# Power.net
KiCad netlist of a schematic drawn in Altium Designer
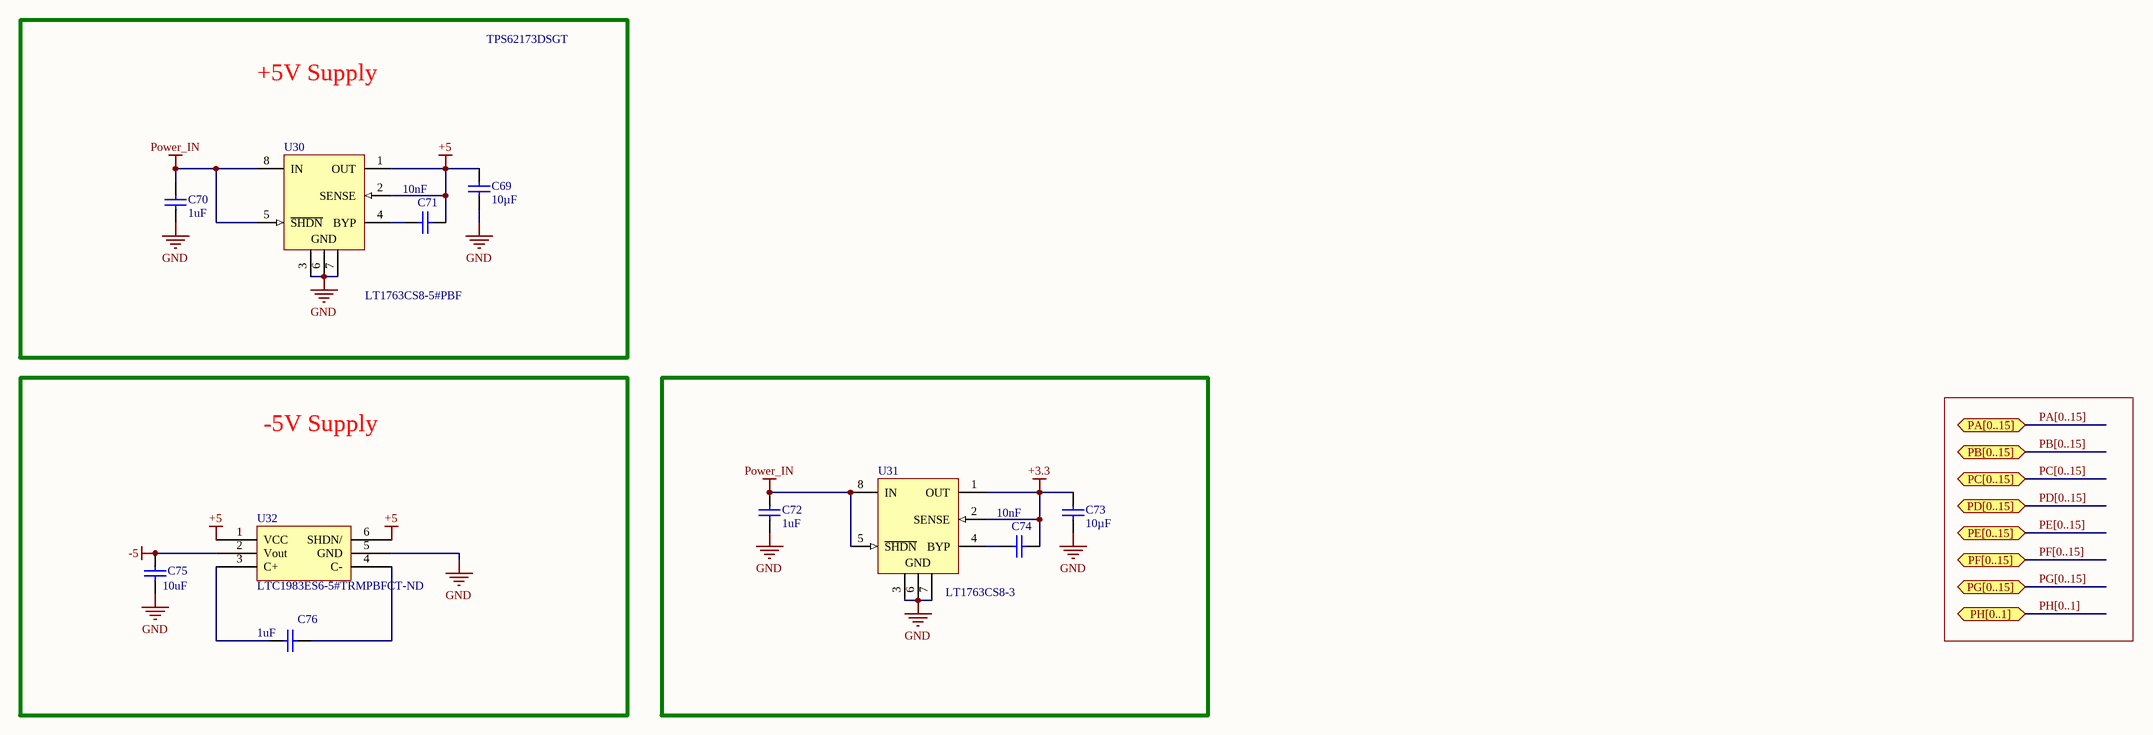
[diagram p0: Power.SchDoc]

(export (version "E")
  (design (tool "Eeschema 10.0.6"))
  (components
    (comp (ref "C69")
      (value "GRM31CR71C106KA12L")
      (footprint "CAPC3216X180X55LL20T25")
      (description "Chip Capacitor, 10 uF, +/- 10%, 16 V, -55 to 125 degC, 1206 (3216 Metric), RoHS, Tape and Reel")
      (fields
        (field (name "TOLERANCE") "10%")
        (field (name "MANUFACTURER") "Murata")
        (field (name "CAPACITY (ELEC.)") "10µF")
      )
      (libsource (lib "Altium Content Vault") (part "CAP-NP-2"))
    )
    (comp (ref "C70")
      (value "C1206C105K5RACTU")
      (footprint "CAPC3216X110X50LL20T25")
      (description "Chip Capacitor, 1 uF, +/- 10%, 50 V, -55 to 125 degC, 1206 (3216 Metric), RoHS, Tape and Reel")
      (fields
        (field (name "CAPACITANCE") "1uF")
        (field (name "MANUFACTURER") "Kemet")
        (field (name "TOLERANCE") "10%")
      )
      (libsource (lib "Altium Content Vault") (part "CAP-NP-2"))
    )
    (comp (ref "C71")
      (value "10nF")
      (footprint "CAPC1206(3216)110_L")
      (description "CAP 10nF 16V ±10% 1206 (3216 Metric) Thickness 1.1mm SMD")
      (fields (field (name "TOLERANCE") "Â±10%") (field (name "Comment") "CAP 10nF 16V 1206(3216)"))
      (libsource (lib "Altium Content Vault") (part "CAP"))
    )
    (comp (ref "C72")
      (value "C1206C105K5RACTU")
      (footprint "CAPC3216X110X50LL20T25")
      (description "Chip Capacitor, 1 uF, +/- 10%, 50 V, -55 to 125 degC, 1206 (3216 Metric), RoHS, Tape and Reel")
      (fields
        (field (name "CAPACITANCE") "1uF")
        (field (name "MANUFACTURER") "Kemet")
        (field (name "TOLERANCE") "10%")
      )
      (libsource (lib "Altium Content Vault") (part "CAP-NP-2"))
    )
    (comp (ref "C73")
      (value "GRM31CR71C106KA12L")
      (footprint "CAPC3216X180X55LL20T25")
      (description "Chip Capacitor, 10 uF, +/- 10%, 16 V, -55 to 125 degC, 1206 (3216 Metric), RoHS, Tape and Reel")
      (fields
        (field (name "TOLERANCE") "10%")
        (field (name "MANUFACTURER") "Murata")
        (field (name "CAPACITY (ELEC.)") "10µF")
      )
      (libsource (lib "Altium Content Vault") (part "CAP-NP-2"))
    )
    (comp (ref "C74")
      (value "10nF")
      (footprint "CAPC1206(3216)110_L")
      (description "CAP 10nF 16V ±10% 1206 (3216 Metric) Thickness 1.1mm SMD")
      (fields (field (name "TOLERANCE") "Â±10%") (field (name "Comment") "CAP 10nF 16V 1206(3216)"))
      (libsource (lib "Altium Content Vault") (part "CAP"))
    )
    (comp (ref "C75")
      (value "JMK316BJ106ML-T")
      (footprint "CAPC1206(3216)130_N")
      (description "10µF ±20% 6.3V Ceramic Capacitor X5R 1206 (3216 Metric)")
      (fields
        (field (name "MANUFACTURER") "Taiyo Yuden")
        (field (name "TOLERANCE") "±20%")
        (field (name "CAPACITANCE") "10uF")
      )
      (libsource (lib "Altium Content Vault") (part "CMP-1037-04913-1"))
    )
    (comp (ref "C76")
      (value "C1206C105K5RACTU")
      (footprint "CAPC3216X110X50LL20T25")
      (description "Chip Capacitor, 1 uF, +/- 10%, 50 V, -55 to 125 degC, 1206 (3216 Metric), RoHS, Tape and Reel")
      (fields
        (field (name "CAPACITANCE") "1uF")
        (field (name "MANUFACTURER") "Kemet")
        (field (name "TOLERANCE") "10%")
      )
      (libsource (lib "Altium Content Vault") (part "CAP-NP-2"))
    )
    (comp (ref "U30")
      (value "LT1763CS8-5#PBF")
      (footprint "LT-S8-8_M")
      (fields (field (name "MANUFACTURER") "Linear Technology"))
      (libsource (lib "Altium Content Vault") (part "LT-LT1763-S8-8"))
    )
    (comp (ref "U31")
      (value "LT1763CS8-3")
      (footprint "LT-S8-8_L")
      (fields (field (name "MANUFACTURER") "Linear Technology"))
      (libsource (lib "Altium Content Vault") (part "LT-LT1763-S8-8"))
    )
    (comp (ref "U32")
      (value "LTC1983ES6-5#TRMPBF")
      (footprint "SOT95P323X100-6N")
      (description "Charge Pump Switching Regulator IC Negative Fixed -5V 1 Output 100mA SOT-23-6 Thin, TSOT-23-6")
      (fields
        (field (name "SUPPLIER PART NUMBER 1") "LTC1983ES6-5#TRMPBFCT-ND")
        (field (name "MANUFACTURER") "Linear Technology/Analog Devices")
        (field (name "BASE PART NUMBER") "LTC1983-5")
      )
      (libsource (lib "ZLS_Schematic_lib") (part "LTC1983ES6-5#TRMPBF"))
    )
  )
  (nets
    (net (code "115") (name "+3.3") (class "Default")
      (node (ref "C73") (pin "2") (pinfunction "2_2") (pintype "passive"))
      (node (ref "C74") (pin "2") (pinfunction "2_2") (pintype "passive"))
      (node (ref "U31") (pin "1") (pinfunction "OUT_1") (pintype "power_in"))
      (node (ref "U31") (pin "2") (pinfunction "SENSE_2") (pintype "input"))
    )
    (net (code "116") (name "+5") (class "Default")
      (node (ref "C69") (pin "2") (pinfunction "2_2") (pintype "passive"))
      (node (ref "C71") (pin "2") (pinfunction "2_2") (pintype "passive"))
      (node (ref "U30") (pin "1") (pinfunction "OUT_1") (pintype "power_in"))
      (node (ref "U30") (pin "2") (pinfunction "SENSE_2") (pintype "input"))
      (node (ref "U32") (pin "1") (pinfunction "VCC_1") (pintype "passive"))
      (node (ref "U32") (pin "6") (pinfunction "SHDN/_6") (pintype "passive"))
    )
    (net (code "117") (name "-5") (class "Default")
      (node (ref "C75") (pin "2") (pinfunction "2_2") (pintype "passive"))
      (node (ref "U32") (pin "2") (pinfunction "Vout_2") (pintype "passive"))
    )
    (net (code "126") (name "GND") (class "Default")
      (node (ref "C69") (pin "1") (pinfunction "1_1") (pintype "passive"))
      (node (ref "C70") (pin "1") (pinfunction "1_1") (pintype "passive"))
      (node (ref "C72") (pin "1") (pinfunction "1_1") (pintype "passive"))
      (node (ref "C73") (pin "1") (pinfunction "1_1") (pintype "passive"))
      (node (ref "C75") (pin "1") (pinfunction "1_1") (pintype "passive"))
      (node (ref "U30") (pin "3") (pinfunction "GND_3") (pintype "power_in"))
      (node (ref "U30") (pin "6") (pinfunction "GND_6") (pintype "power_in"))
      (node (ref "U30") (pin "7") (pinfunction "GND_7") (pintype "power_in"))
      (node (ref "U31") (pin "3") (pinfunction "GND_3") (pintype "power_in"))
      (node (ref "U31") (pin "6") (pinfunction "GND_6") (pintype "power_in"))
      (node (ref "U31") (pin "7") (pinfunction "GND_7") (pintype "power_in"))
      (node (ref "U32") (pin "5") (pinfunction "GND_5") (pintype "passive"))
    )
    (net (code "127") (name "Net-(U30-BYP)") (class "Default")
      (node (ref "C71") (pin "1") (pinfunction "1_1") (pintype "passive"))
      (node (ref "U30") (pin "4") (pinfunction "BYP_4") (pintype "passive"))
    )
    (net (code "128") (name "Net-(U31-BYP)") (class "Default")
      (node (ref "C74") (pin "1") (pinfunction "1_1") (pintype "passive"))
      (node (ref "U31") (pin "4") (pinfunction "BYP_4") (pintype "passive"))
    )
    (net (code "129") (name "Net-(U32-C+)") (class "Default")
      (node (ref "C76") (pin "1") (pinfunction "1_1") (pintype "passive"))
      (node (ref "U32") (pin "3") (pinfunction "C+_3") (pintype "passive"))
    )
    (net (code "130") (name "Net-(U32-C-)") (class "Default")
      (node (ref "C76") (pin "2") (pinfunction "2_2") (pintype "passive"))
      (node (ref "U32") (pin "4") (pinfunction "C-_4") (pintype "passive"))
    )
    (net (code "131") (name "Power_IN") (class "Default")
      (node (ref "C70") (pin "2") (pinfunction "2_2") (pintype "passive"))
      (node (ref "C72") (pin "2") (pinfunction "2_2") (pintype "passive"))
      (node (ref "U30") (pin "5") (pinfunction "~{SHDN}_5") (pintype "input"))
      (node (ref "U30") (pin "8") (pinfunction "IN_8") (pintype "power_in"))
      (node (ref "U31") (pin "5") (pinfunction "~{SHDN}_5") (pintype "input"))
      (node (ref "U31") (pin "8") (pinfunction "IN_8") (pintype "power_in"))
    )
  )
)
